# GPIO_COMM.net
KiCad netlist of a schematic drawn in Altium Designer
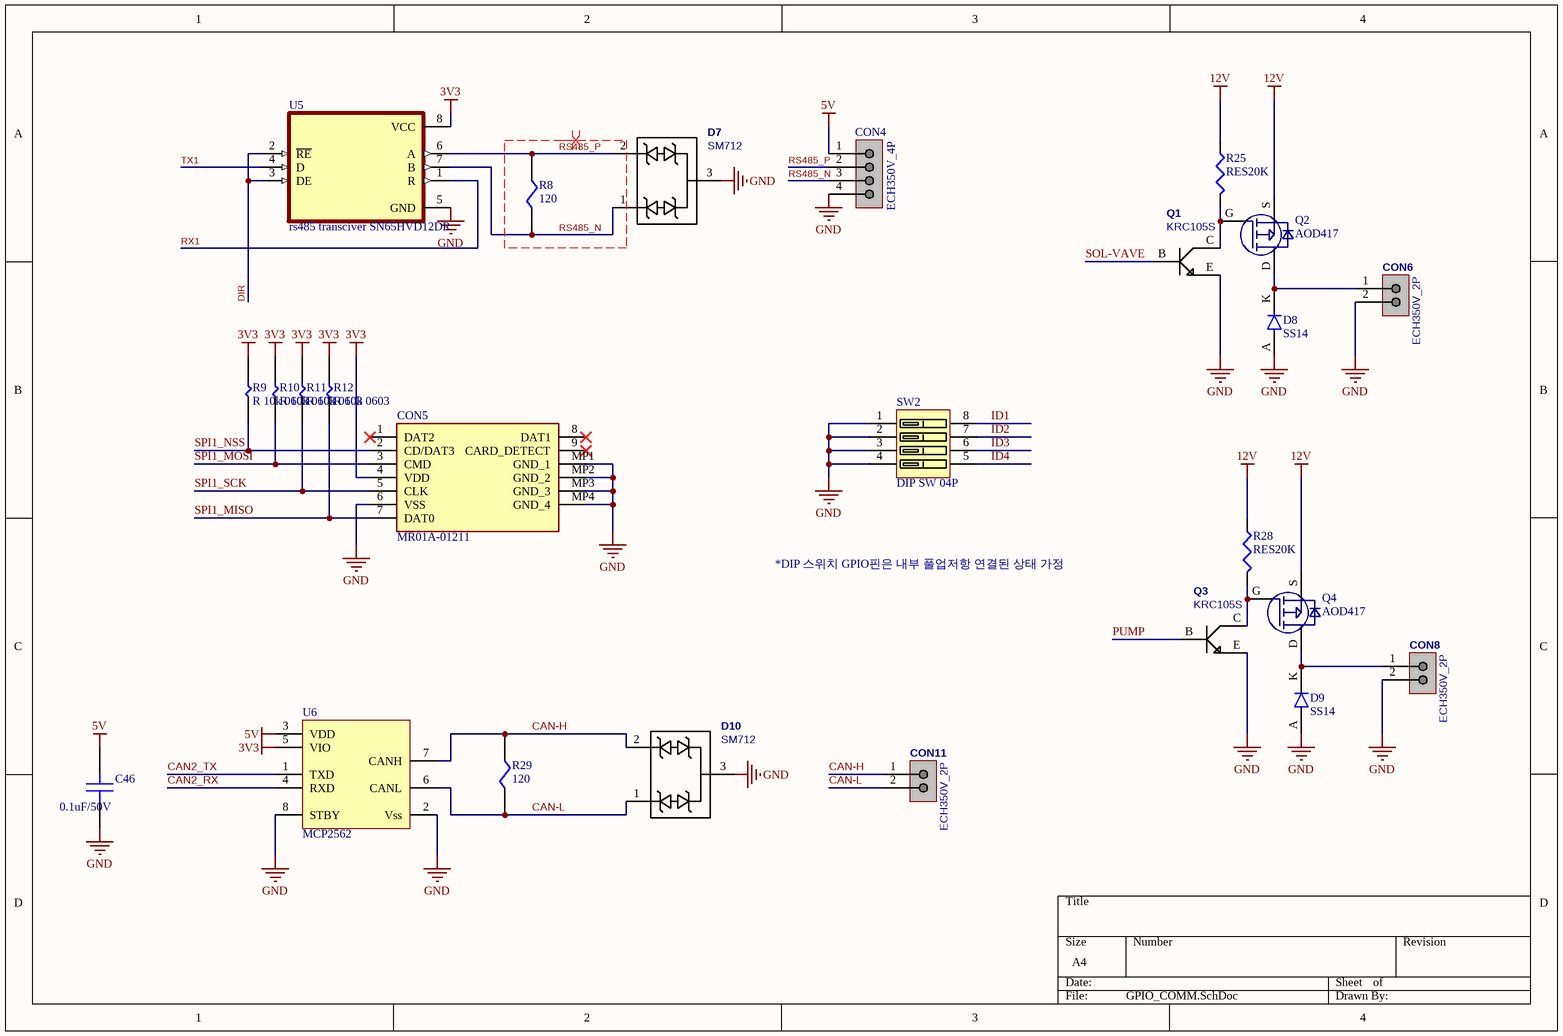
[diagram p0: GPIO_COMM.SchDoc]

(export (version "E")
  (design (tool "Eeschema 10.0.6"))
  (components
    (comp (ref "C46")
      (value "0.1uF/50V")
      (footprint "CAP0.1u_0603_ceramic")
      (description "cap, 0.1u 0603, 50V")
      (libsource (lib "MyLIB240624") (part "CAP0.1u_0603_ceramic"))
    )
    (comp (ref "CON4")
      (value "ECH350V_4P")
      (footprint "CON4P_ECH350V")
      (description "Connector, Terminal block 4p_ECH350V")
      (libsource (lib "SensoMonitor") (part "CON4P_ECH350V"))
    )
    (comp (ref "CON5")
      (value "MR01A-01211")
      (footprint "MR01A-01211")
      (description "MicroSD Card Connector")
      (libsource (lib "SensoMonitor") (part "MR01A-01211"))
    )
    (comp (ref "CON6")
      (value "ECH350V_2P")
      (footprint "CON2P_ECH350V")
      (description "Header box, Header2x1_ECH350V")
      (libsource (lib "SensoMonitor") (part "CON2P_ECH350V"))
    )
    (comp (ref "CON8")
      (value "ECH350V_2P")
      (footprint "CON2P_ECH350V")
      (description "Header box, Header2x1_ECH350V")
      (libsource (lib "SensoMonitor") (part "CON2P_ECH350V"))
    )
    (comp (ref "CON11")
      (value "ECH350V_2P")
      (footprint "CON2P_ECH350V")
      (description "Header box, Header2x1_ECH350V")
      (libsource (lib "SensoMonitor") (part "CON2P_ECH350V"))
    )
    (comp (ref "D7")
      (value "SM712")
      (footprint "SM712")
      (description "SM712 Series 600W Asymmetrical TVS Diode Array")
      (libsource (lib "SensoMonitor") (part "SM712"))
    )
    (comp (ref "D8")
      (value "SS14")
      (footprint "DO-214AC")
      (description "Schottky Barrier Rectifiers")
      (libsource (lib "MyLIB240624") (part "SS14"))
    )
    (comp (ref "D9")
      (value "SS14")
      (footprint "DO-214AC")
      (description "Schottky Barrier Rectifiers")
      (libsource (lib "MyLIB240624") (part "SS14"))
    )
    (comp (ref "D10")
      (value "SM712")
      (footprint "SM712")
      (description "SM712 Series 600W Asymmetrical TVS Diode Array")
      (libsource (lib "SensoMonitor") (part "SM712"))
    )
    (comp (ref "Q1")
      (value "KRC105S")
      (footprint "NPN_KRC105S")
      (libsource (lib "SensoMonitor") (part "NPN_KRC105S"))
    )
    (comp (ref "Q2")
      (value "AOD417")
      (footprint "P-MOSFET_AOD417")
      (libsource (lib "SensoMonitor") (part "P-MOSFET_AOD417"))
    )
    (comp (ref "Q3")
      (value "KRC105S")
      (footprint "NPN_KRC105S")
      (libsource (lib "SensoMonitor") (part "NPN_KRC105S"))
    )
    (comp (ref "Q4")
      (value "AOD417")
      (footprint "P-MOSFET_AOD417")
      (libsource (lib "SensoMonitor") (part "P-MOSFET_AOD417"))
    )
    (comp (ref "R8")
      (value "120")
      (footprint "RES120_0805")
      (libsource (lib "RES120_0805") (part "RES120_0805"))
    )
    (comp (ref "R9")
      (value "R 10k 0603")
      (footprint "RES10K_0603")
      (libsource (lib "MyLIB240624") (part "RES10K_0603"))
    )
    (comp (ref "R10")
      (value "R 10k 0603")
      (footprint "RES10K_0603")
      (libsource (lib "MyLIB240624") (part "RES10K_0603"))
    )
    (comp (ref "R11")
      (value "R 10k 0603")
      (footprint "RES10K_0603")
      (libsource (lib "MyLIB240624") (part "RES10K_0603"))
    )
    (comp (ref "R12")
      (value "R 10k 0603")
      (footprint "RES10K_0603")
      (libsource (lib "MyLIB240624") (part "RES10K_0603"))
    )
    (comp (ref "R25")
      (value "RES20K")
      (footprint "RES20K_0603")
      (description "RES20K_0603")
      (libsource (lib "SensoMonitor") (part "RES20K"))
    )
    (comp (ref "R28")
      (value "RES20K")
      (footprint "RES20K_0603")
      (description "RES20K_0603")
      (libsource (lib "SensoMonitor") (part "RES20K"))
    )
    (comp (ref "R29")
      (value "120")
      (footprint "RES120_0805")
      (libsource (lib "RES120_0805") (part "RES120_0805"))
    )
    (comp (ref "SW2")
      (value "DIP SW 04P")
      (footprint "DIP SW 04P SMD (KHS42)")
      (description "Switch")
      (libsource (lib "MyLIB240624") (part "DIP SW 04P"))
    )
    (comp (ref "U5")
      (value "rs485 transciver SN65HVD12DR")
      (footprint "RS485_Transciver_SN65HVD12DR")
      (libsource (lib "MyLIB240624") (part "RS485_Transciver_SN65HVD12DR"))
    )
    (comp (ref "U6")
      (value "MCP2562")
      (footprint "[CAN]MCP2562")
      (description "CAN Transceiver, SOIC127P600X175-8N, MCP2562-E/SN")
      (libsource (lib "SensoMonitor") (part "[CAN]MCP2562"))
    )
  )
  (nets
    (net (code "1") (name "/CAN-H") (class "Default")
      (node (ref "CON11") (pin "1") (pinfunction "150_1") (pintype "passive"))
      (node (ref "D10") (pin "2") (pinfunction "146_2") (pintype "passive"))
      (node (ref "R29") (pin "2") (pinfunction "2_2") (pintype "passive"))
      (node (ref "U6") (pin "7") (pinfunction "CANH_7") (pintype "passive"))
    )
    (net (code "2") (name "/CAN-L") (class "Default")
      (node (ref "CON11") (pin "2") (pinfunction "150_2") (pintype "passive"))
      (node (ref "D10") (pin "1") (pinfunction "146_1") (pintype "passive"))
      (node (ref "R29") (pin "1") (pinfunction "1_1") (pintype "passive"))
      (node (ref "U6") (pin "6") (pinfunction "CANL_6") (pintype "passive"))
    )
    (net (code "3") (name "/CAN2_RX") (class "Default")
      (node (ref "U6") (pin "4") (pinfunction "RXD_4") (pintype "passive"))
    )
    (net (code "4") (name "/CAN2_TX") (class "Default")
      (node (ref "U6") (pin "1") (pinfunction "TXD_1") (pintype "passive"))
    )
    (net (code "5") (name "/DIR") (class "Default")
      (node (ref "U5") (pin "2") (pinfunction "~{RE}_2") (pintype "input"))
      (node (ref "U5") (pin "3") (pinfunction "DE_3") (pintype "input"))
    )
    (net (code "6") (name "/ID1") (class "Default")
      (node (ref "SW2") (pin "8") (pinfunction "170_8") (pintype "passive"))
    )
    (net (code "7") (name "/ID2") (class "Default")
      (node (ref "SW2") (pin "7") (pinfunction "169_7") (pintype "passive"))
    )
    (net (code "8") (name "/ID3") (class "Default")
      (node (ref "SW2") (pin "6") (pinfunction "168_6") (pintype "passive"))
    )
    (net (code "9") (name "/ID4") (class "Default")
      (node (ref "SW2") (pin "5") (pinfunction "167_5") (pintype "passive"))
    )
    (net (code "10") (name "/PUMP") (class "Default")
      (node (ref "Q3") (pin "B") (pinfunction "185_B") (pintype "passive"))
    )
    (net (code "11") (name "/RS485_N") (class "Default")
      (node (ref "CON4") (pin "3") (pinfunction "150_3") (pintype "passive"))
      (node (ref "D7") (pin "1") (pinfunction "146_1") (pintype "passive"))
      (node (ref "R8") (pin "1") (pinfunction "1_1") (pintype "passive"))
      (node (ref "U5") (pin "7") (pinfunction "B_7") (pintype "output"))
    )
    (net (code "12") (name "/RS485_P") (class "Default")
      (node (ref "CON4") (pin "2") (pinfunction "150_2") (pintype "passive"))
      (node (ref "D7") (pin "2") (pinfunction "146_2") (pintype "passive"))
      (node (ref "R8") (pin "2") (pinfunction "2_2") (pintype "passive"))
      (node (ref "U5") (pin "6") (pinfunction "A_6") (pintype "output"))
    )
    (net (code "13") (name "/RX1") (class "Default")
      (node (ref "U5") (pin "1") (pinfunction "R_1") (pintype "output"))
    )
    (net (code "14") (name "/SOL-VAVE") (class "Default")
      (node (ref "Q1") (pin "B") (pinfunction "185_B") (pintype "passive"))
    )
    (net (code "15") (name "/SPI1_MISO") (class "Default")
      (node (ref "CON5") (pin "7") (pinfunction "DAT0_7") (pintype "passive"))
      (node (ref "R12") (pin "1") (pinfunction "1_1") (pintype "passive"))
    )
    (net (code "16") (name "/SPI1_MOSI") (class "Default")
      (node (ref "CON5") (pin "3") (pinfunction "CMD_3") (pintype "passive"))
      (node (ref "R10") (pin "1") (pinfunction "1_1") (pintype "passive"))
    )
    (net (code "17") (name "/SPI1_NSS") (class "Default")
      (node (ref "CON5") (pin "2") (pinfunction "CD/DAT3_2") (pintype "passive"))
      (node (ref "R9") (pin "1") (pinfunction "1_1") (pintype "passive"))
    )
    (net (code "18") (name "/SPI1_SCK") (class "Default")
      (node (ref "CON5") (pin "5") (pinfunction "CLK_5") (pintype "passive"))
      (node (ref "R11") (pin "1") (pinfunction "1_1") (pintype "passive"))
    )
    (net (code "19") (name "/TX1") (class "Default")
      (node (ref "U5") (pin "4") (pinfunction "D_4") (pintype "input"))
    )
    (net (code "20") (name "3V3") (class "Default")
      (node (ref "CON5") (pin "4") (pinfunction "VDD_4") (pintype "passive"))
      (node (ref "R10") (pin "2") (pinfunction "2_2") (pintype "passive"))
      (node (ref "R11") (pin "2") (pinfunction "2_2") (pintype "passive"))
      (node (ref "R12") (pin "2") (pinfunction "2_2") (pintype "passive"))
      (node (ref "R9") (pin "2") (pinfunction "2_2") (pintype "passive"))
      (node (ref "U5") (pin "8") (pinfunction "VCC_8") (pintype "power_in"))
      (node (ref "U6") (pin "5") (pinfunction "VIO_5") (pintype "passive"))
    )
    (net (code "21") (name "5V") (class "Default")
      (node (ref "C46") (pin "2") (pinfunction "2_2") (pintype "passive"))
      (node (ref "CON4") (pin "1") (pinfunction "150_1") (pintype "passive"))
      (node (ref "U6") (pin "3") (pinfunction "VDD_3") (pintype "passive"))
    )
    (net (code "22") (name "12V") (class "Default")
      (node (ref "Q2") (pin "S") (pinfunction "74_S") (pintype "passive"))
      (node (ref "Q4") (pin "S") (pinfunction "74_S") (pintype "passive"))
      (node (ref "R25") (pin "1") (pinfunction "1_1") (pintype "passive"))
      (node (ref "R28") (pin "1") (pinfunction "1_1") (pintype "passive"))
    )
    (net (code "23") (name "GND") (class "Default")
      (node (ref "C46") (pin "1") (pinfunction "1_1") (pintype "passive"))
      (node (ref "CON4") (pin "4") (pinfunction "150_4") (pintype "passive"))
      (node (ref "CON5") (pin "6") (pinfunction "VSS_6") (pintype "passive"))
      (node (ref "CON5") (pin "MP1") (pinfunction "GND_1_MP1") (pintype "passive"))
      (node (ref "CON5") (pin "MP2") (pinfunction "GND_2_MP2") (pintype "passive"))
      (node (ref "CON5") (pin "MP3") (pinfunction "GND_3_MP3") (pintype "passive"))
      (node (ref "CON5") (pin "MP4") (pinfunction "GND_4_MP4") (pintype "passive"))
      (node (ref "CON6") (pin "2") (pinfunction "150_2") (pintype "passive"))
      (node (ref "CON8") (pin "2") (pinfunction "150_2") (pintype "passive"))
      (node (ref "D10") (pin "3") (pinfunction "146_3") (pintype "passive"))
      (node (ref "D7") (pin "3") (pinfunction "146_3") (pintype "passive"))
      (node (ref "D8") (pin "A") (pinfunction "A_A") (pintype "passive"))
      (node (ref "D9") (pin "A") (pinfunction "A_A") (pintype "passive"))
      (node (ref "Q1") (pin "E") (pinfunction "185_E") (pintype "passive"))
      (node (ref "Q3") (pin "E") (pinfunction "185_E") (pintype "passive"))
      (node (ref "SW2") (pin "1") (pinfunction "167_1") (pintype "passive"))
      (node (ref "SW2") (pin "2") (pinfunction "168_2") (pintype "passive"))
      (node (ref "SW2") (pin "3") (pinfunction "169_3") (pintype "passive"))
      (node (ref "SW2") (pin "4") (pinfunction "170_4") (pintype "passive"))
      (node (ref "U5") (pin "5") (pinfunction "GND_5") (pintype "power_in"))
      (node (ref "U6") (pin "2") (pinfunction "Vss_2") (pintype "passive"))
      (node (ref "U6") (pin "8") (pinfunction "STBY_8") (pintype "passive"))
    )
    (net (code "24") (name "Net-(CON6-150-Pad1)") (class "Default")
      (node (ref "CON6") (pin "1") (pinfunction "150_1") (pintype "passive"))
      (node (ref "D8") (pin "K") (pinfunction "K_K") (pintype "passive"))
      (node (ref "Q2") (pin "D") (pinfunction "74_D") (pintype "passive"))
    )
    (net (code "25") (name "Net-(CON8-150-Pad1)") (class "Default")
      (node (ref "CON8") (pin "1") (pinfunction "150_1") (pintype "passive"))
      (node (ref "D9") (pin "K") (pinfunction "K_K") (pintype "passive"))
      (node (ref "Q4") (pin "D") (pinfunction "74_D") (pintype "passive"))
    )
    (net (code "26") (name "Net-(Q1-185-PadC)") (class "Default")
      (node (ref "Q1") (pin "C") (pinfunction "185_C") (pintype "passive"))
      (node (ref "Q2") (pin "G") (pinfunction "74_G") (pintype "passive"))
      (node (ref "R25") (pin "2") (pinfunction "2_2") (pintype "passive"))
    )
    (net (code "27") (name "Net-(Q3-185-PadC)") (class "Default")
      (node (ref "Q3") (pin "C") (pinfunction "185_C") (pintype "passive"))
      (node (ref "Q4") (pin "G") (pinfunction "74_G") (pintype "passive"))
      (node (ref "R28") (pin "2") (pinfunction "2_2") (pintype "passive"))
    )
    (net (code "28") (name "unconnected-(CON5-CARD_DETECT-Pad9)") (class "Default")
      (node (ref "CON5") (pin "9") (pinfunction "CARD_DETECT_9") (pintype "passive+no_connect"))
    )
    (net (code "29") (name "unconnected-(CON5-DAT1-Pad8)") (class "Default")
      (node (ref "CON5") (pin "8") (pinfunction "DAT1_8") (pintype "passive+no_connect"))
    )
    (net (code "30") (name "unconnected-(CON5-DAT2-Pad1)") (class "Default")
      (node (ref "CON5") (pin "1") (pinfunction "DAT2_1") (pintype "passive+no_connect"))
    )
  )
)
